# display.net
KiCad netlist of a schematic drawn in EAGLE
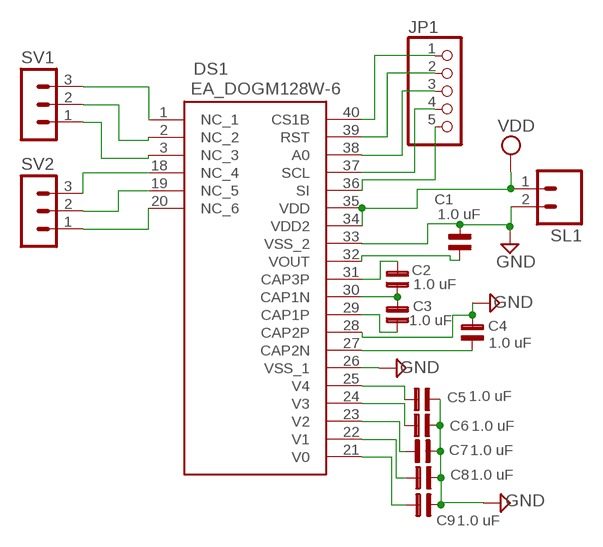
[diagram p0: schematic, sheet 1]

(export (version "E")
  (design (tool "Eeschema 10.0.6"))
  (components
    (comp (ref "C1")
      (value "1.0 uF")
      (footprint "eagle-import:0805")
      (libsource (lib "eagle-import") (part "C0805"))
    )
    (comp (ref "C2")
      (value "1.0 uF")
      (footprint "eagle-import:0805")
      (libsource (lib "eagle-import") (part "C0805"))
    )
    (comp (ref "C3")
      (value "1.0 uF")
      (footprint "eagle-import:0805")
      (libsource (lib "eagle-import") (part "C0805"))
    )
    (comp (ref "C4")
      (value "1.0 uF")
      (footprint "eagle-import:0805")
      (libsource (lib "eagle-import") (part "C0805"))
    )
    (comp (ref "C5")
      (value "1.0 uF")
      (footprint "eagle-import:0805")
      (libsource (lib "eagle-import") (part "C0805"))
    )
    (comp (ref "C6")
      (value "1.0 uF")
      (footprint "eagle-import:0805")
      (libsource (lib "eagle-import") (part "C0805"))
    )
    (comp (ref "C7")
      (value "1.0 uF")
      (footprint "eagle-import:0805")
      (libsource (lib "eagle-import") (part "C0805"))
    )
    (comp (ref "C8")
      (value "1.0 uF")
      (footprint "eagle-import:0805")
      (libsource (lib "eagle-import") (part "C0805"))
    )
    (comp (ref "C9")
      (value "1.0 uF")
      (footprint "eagle-import:0805")
      (libsource (lib "eagle-import") (part "C0805"))
    )
    (comp (ref "DS1")
      (value "EA_DOGM128W-6")
      (footprint "eagle-import:EADOGM128W6")
      (fields
        (field (name "ARROW_PART_NUMBER") "EA DOGM128W-6")
        (field (name "MOUSER_PART_NUMBER") "790-EADOGM128W6")
      )
      (libsource (lib "eagle-import") (part "EA_DOGM128W-6"))
    )
    (comp (ref "JP1")
      (value "PINHD-1X5")
      (footprint "eagle-import:1X05")
      (libsource (lib "eagle-import") (part "PINHD-1X5"))
    )
    (comp (ref "SL1")
      (value "M02")
      (footprint "eagle-import:02P")
      (libsource (lib "eagle-import") (part "M02"))
    )
    (comp (ref "SV1")
      (value "MA03-1")
      (footprint "eagle-import:MA03-1")
      (libsource (lib "eagle-import") (part "MA03-1"))
    )
    (comp (ref "SV2")
      (value "MA03-1")
      (footprint "eagle-import:MA03-1")
      (libsource (lib "eagle-import") (part "MA03-1"))
    )
  )
  (nets
    (net (code "1") (name "GND") (class "Default")
      (node (ref "C1") (pin "2") (pinfunction "2_2") (pintype "passive"))
      (node (ref "C4") (pin "2") (pinfunction "2_2") (pintype "passive"))
      (node (ref "C5") (pin "2") (pinfunction "2_2") (pintype "passive"))
      (node (ref "C6") (pin "2") (pinfunction "2_2") (pintype "passive"))
      (node (ref "C7") (pin "2") (pinfunction "2_2") (pintype "passive"))
      (node (ref "C8") (pin "2") (pinfunction "2_2") (pintype "passive"))
      (node (ref "C9") (pin "2") (pinfunction "2_2") (pintype "passive"))
      (node (ref "DS1") (pin "26") (pinfunction "VSS_1_26") (pintype "bidirectional"))
      (node (ref "DS1") (pin "28") (pinfunction "CAP2P_28") (pintype "bidirectional"))
      (node (ref "DS1") (pin "33") (pinfunction "VSS_2_33") (pintype "bidirectional"))
      (node (ref "SL1") (pin "2") (pinfunction "2_2") (pintype "passive"))
    )
    (net (code "2") (name "Net-(DS1-A0)") (class "Default")
      (node (ref "DS1") (pin "38") (pinfunction "A0_38") (pintype "bidirectional"))
      (node (ref "JP1") (pin "3") (pinfunction "3_3") (pintype "passive"))
    )
    (net (code "3") (name "Net-(DS1-CAP1N)") (class "Default")
      (node (ref "C2") (pin "1") (pinfunction "1_1") (pintype "passive"))
      (node (ref "C3") (pin "2") (pinfunction "2_2") (pintype "passive"))
      (node (ref "DS1") (pin "30") (pinfunction "CAP1N_30") (pintype "bidirectional"))
    )
    (net (code "4") (name "Net-(DS1-CAP1P)") (class "Default")
      (node (ref "C3") (pin "1") (pinfunction "1_1") (pintype "passive"))
      (node (ref "DS1") (pin "29") (pinfunction "CAP1P_29") (pintype "bidirectional"))
    )
    (net (code "5") (name "Net-(DS1-CAP2N)") (class "Default")
      (node (ref "C4") (pin "1") (pinfunction "1_1") (pintype "passive"))
      (node (ref "DS1") (pin "27") (pinfunction "CAP2N_27") (pintype "bidirectional"))
    )
    (net (code "6") (name "Net-(DS1-CAP3P)") (class "Default")
      (node (ref "C2") (pin "2") (pinfunction "2_2") (pintype "passive"))
      (node (ref "DS1") (pin "31") (pinfunction "CAP3P_31") (pintype "bidirectional"))
    )
    (net (code "7") (name "Net-(DS1-CS1B)") (class "Default")
      (node (ref "DS1") (pin "40") (pinfunction "CS1B_40") (pintype "bidirectional"))
      (node (ref "JP1") (pin "1") (pinfunction "1_1") (pintype "passive"))
    )
    (net (code "8") (name "Net-(DS1-NC_1)") (class "Default")
      (node (ref "DS1") (pin "1") (pinfunction "NC_1_1") (pintype "bidirectional"))
      (node (ref "SV1") (pin "3") (pinfunction "3_3") (pintype "passive"))
    )
    (net (code "9") (name "Net-(DS1-NC_2)") (class "Default")
      (node (ref "DS1") (pin "2") (pinfunction "NC_2_2") (pintype "bidirectional"))
      (node (ref "SV1") (pin "2") (pinfunction "2_2") (pintype "passive"))
    )
    (net (code "10") (name "Net-(DS1-NC_3)") (class "Default")
      (node (ref "DS1") (pin "3") (pinfunction "NC_3_3") (pintype "bidirectional"))
      (node (ref "SV1") (pin "1") (pinfunction "1_1") (pintype "passive"))
    )
    (net (code "11") (name "Net-(DS1-NC_4)") (class "Default")
      (node (ref "DS1") (pin "18") (pinfunction "NC_4_18") (pintype "bidirectional"))
      (node (ref "SV2") (pin "3") (pinfunction "3_3") (pintype "passive"))
    )
    (net (code "12") (name "Net-(DS1-NC_5)") (class "Default")
      (node (ref "DS1") (pin "19") (pinfunction "NC_5_19") (pintype "bidirectional"))
      (node (ref "SV2") (pin "2") (pinfunction "2_2") (pintype "passive"))
    )
    (net (code "13") (name "Net-(DS1-NC_6)") (class "Default")
      (node (ref "DS1") (pin "20") (pinfunction "NC_6_20") (pintype "bidirectional"))
      (node (ref "SV2") (pin "1") (pinfunction "1_1") (pintype "passive"))
    )
    (net (code "14") (name "Net-(DS1-RST)") (class "Default")
      (node (ref "DS1") (pin "39") (pinfunction "RST_39") (pintype "bidirectional"))
      (node (ref "JP1") (pin "2") (pinfunction "2_2") (pintype "passive"))
    )
    (net (code "15") (name "Net-(DS1-SCL)") (class "Default")
      (node (ref "DS1") (pin "37") (pinfunction "SCL_37") (pintype "bidirectional"))
      (node (ref "JP1") (pin "4") (pinfunction "4_4") (pintype "passive"))
    )
    (net (code "16") (name "Net-(DS1-SI)") (class "Default")
      (node (ref "DS1") (pin "36") (pinfunction "SI_36") (pintype "bidirectional"))
      (node (ref "JP1") (pin "5") (pinfunction "5_5") (pintype "passive"))
    )
    (net (code "17") (name "Net-(DS1-V0)") (class "Default")
      (node (ref "C9") (pin "1") (pinfunction "1_1") (pintype "passive"))
      (node (ref "DS1") (pin "21") (pinfunction "V0_21") (pintype "bidirectional"))
    )
    (net (code "18") (name "Net-(DS1-V1)") (class "Default")
      (node (ref "C8") (pin "1") (pinfunction "1_1") (pintype "passive"))
      (node (ref "DS1") (pin "22") (pinfunction "V1_22") (pintype "bidirectional"))
    )
    (net (code "19") (name "Net-(DS1-V2)") (class "Default")
      (node (ref "C7") (pin "1") (pinfunction "1_1") (pintype "passive"))
      (node (ref "DS1") (pin "23") (pinfunction "V2_23") (pintype "bidirectional"))
    )
    (net (code "20") (name "Net-(DS1-V3)") (class "Default")
      (node (ref "C6") (pin "1") (pinfunction "1_1") (pintype "passive"))
      (node (ref "DS1") (pin "24") (pinfunction "V3_24") (pintype "bidirectional"))
    )
    (net (code "21") (name "Net-(DS1-V4)") (class "Default")
      (node (ref "C5") (pin "1") (pinfunction "1_1") (pintype "passive"))
      (node (ref "DS1") (pin "25") (pinfunction "V4_25") (pintype "bidirectional"))
    )
    (net (code "22") (name "Net-(DS1-VOUT)") (class "Default")
      (node (ref "C1") (pin "1") (pinfunction "1_1") (pintype "passive"))
      (node (ref "DS1") (pin "32") (pinfunction "VOUT_32") (pintype "bidirectional"))
    )
    (net (code "23") (name "VDD") (class "Default")
      (node (ref "DS1") (pin "34") (pinfunction "VDD2_34") (pintype "bidirectional"))
      (node (ref "DS1") (pin "35") (pinfunction "VDD_35") (pintype "bidirectional"))
      (node (ref "SL1") (pin "1") (pinfunction "1_1") (pintype "passive"))
    )
  )
)
